# PotDivMUXwithOP_v9.net
KiCad netlist of a schematic drawn in EAGLE
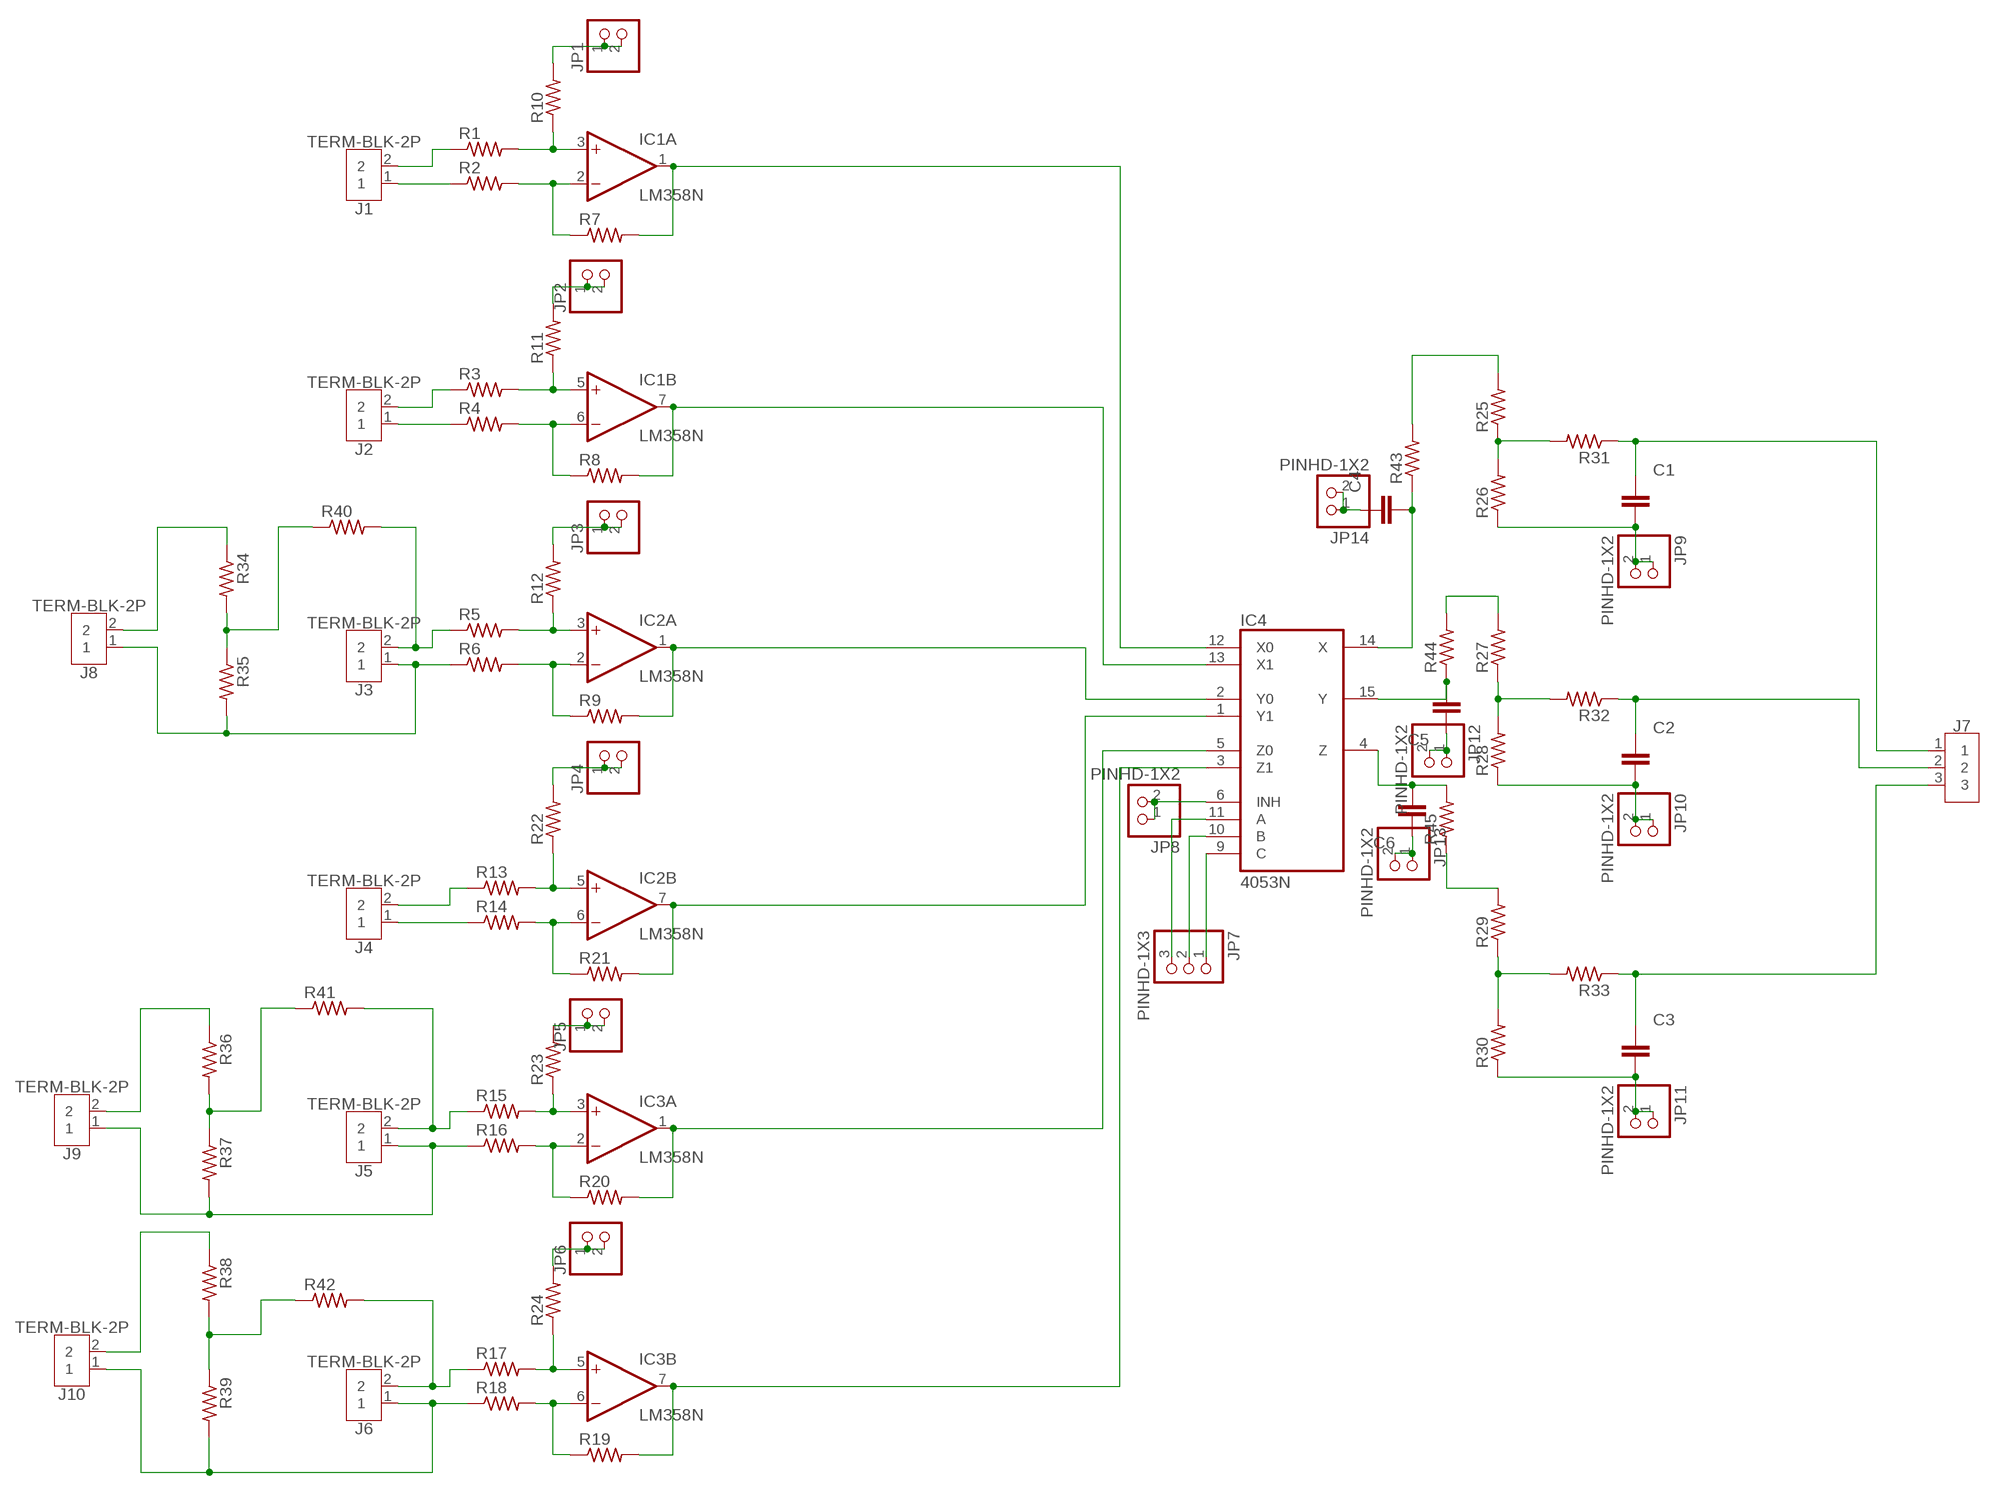
[diagram p0: schematic, sheet 1]

(export (version "E")
  (design (tool "Eeschema 10.0.6"))
  (components
    (comp (ref "C1")
      (value "C_RADIAL-12.5MM-DIA")
      (footprint "eagle-import:CAPRD550W60D1025H1250B")
      (libsource (lib "eagle-import") (part "CRADIAL-12.5MM-DIA_"))
    )
    (comp (ref "C2")
      (value "C_RADIAL-12.5MM-DIA")
      (footprint "eagle-import:CAPRD550W60D1025H1250B")
      (libsource (lib "eagle-import") (part "CRADIAL-12.5MM-DIA_"))
    )
    (comp (ref "C3")
      (value "C_RADIAL-12.5MM-DIA")
      (footprint "eagle-import:CAPRD550W60D1025H1250B")
      (libsource (lib "eagle-import") (part "CRADIAL-12.5MM-DIA_"))
    )
    (comp (ref "C4")
      (value "C_RADIAL-12.5MM-DIA")
      (footprint "eagle-import:CAPRD550W60D1025H1250B")
      (libsource (lib "eagle-import") (part "CRADIAL-12.5MM-DIA_"))
    )
    (comp (ref "C5")
      (value "C_RADIAL-12.5MM-DIA")
      (footprint "eagle-import:CAPRD550W60D1025H1250B")
      (libsource (lib "eagle-import") (part "CRADIAL-12.5MM-DIA_"))
    )
    (comp (ref "C6")
      (value "C_RADIAL-12.5MM-DIA")
      (footprint "eagle-import:CAPRD550W60D1025H1250B")
      (libsource (lib "eagle-import") (part "CRADIAL-12.5MM-DIA_"))
    )
    (comp (ref "IC1")
      (value "LM358N")
      (footprint "eagle-import:DIL08")
      (libsource (lib "eagle-import") (part "LM358N"))
    )
    (comp (ref "IC2")
      (value "LM358N")
      (footprint "eagle-import:DIL08")
      (libsource (lib "eagle-import") (part "LM358N"))
    )
    (comp (ref "IC3")
      (value "LM358N")
      (footprint "eagle-import:DIL08")
      (libsource (lib "eagle-import") (part "LM358N"))
    )
    (comp (ref "IC4")
      (value "4053N")
      (footprint "eagle-import:DIL16")
      (libsource (lib "eagle-import") (part "4053N"))
    )
    (comp (ref "J1")
      (value "TERM-BLK-2P")
      (footprint "eagle-import:TERMBLK_508-2N")
      (fields (field (name "MANUFACTURER") "TE Connectivity AMP Connectors") (field (name "MPN") "282837-2"))
      (libsource (lib "eagle-import") (part "2828XX-2282837-2"))
    )
    (comp (ref "J2")
      (value "TERM-BLK-2P")
      (footprint "eagle-import:TERMBLK_508-2N")
      (fields (field (name "MANUFACTURER") "TE Connectivity AMP Connectors") (field (name "MPN") "282837-2"))
      (libsource (lib "eagle-import") (part "2828XX-2282837-2"))
    )
    (comp (ref "J3")
      (value "TERM-BLK-2P")
      (footprint "eagle-import:TERMBLK_508-2N")
      (fields (field (name "MANUFACTURER") "TE Connectivity AMP Connectors") (field (name "MPN") "282837-2"))
      (libsource (lib "eagle-import") (part "2828XX-2282837-2"))
    )
    (comp (ref "J4")
      (value "TERM-BLK-2P")
      (footprint "eagle-import:TERMBLK_508-2N")
      (fields (field (name "MANUFACTURER") "TE Connectivity AMP Connectors") (field (name "MPN") "282837-2"))
      (libsource (lib "eagle-import") (part "2828XX-2282837-2"))
    )
    (comp (ref "J5")
      (value "TERM-BLK-2P")
      (footprint "eagle-import:TERMBLK_508-2N")
      (fields (field (name "MANUFACTURER") "TE Connectivity AMP Connectors") (field (name "MPN") "282837-2"))
      (libsource (lib "eagle-import") (part "2828XX-2282837-2"))
    )
    (comp (ref "J6")
      (value "TERM-BLK-2P")
      (footprint "eagle-import:TERMBLK_508-2N")
      (fields (field (name "MANUFACTURER") "TE Connectivity AMP Connectors") (field (name "MPN") "282837-2"))
      (libsource (lib "eagle-import") (part "2828XX-2282837-2"))
    )
    (comp (ref "J7")
      (value "TERM-BLK-3P")
      (footprint "eagle-import:TERMBLK_508-3N")
      (fields (field (name "MANUFACTURER") "TE Connectivity") (field (name "MPN") "282837-3"))
      (libsource (lib "eagle-import") (part "2828XX-3282837-3"))
    )
    (comp (ref "J8")
      (value "TERM-BLK-2P")
      (footprint "eagle-import:TERMBLK_508-2N")
      (fields (field (name "MANUFACTURER") "TE Connectivity AMP Connectors") (field (name "MPN") "282837-2"))
      (libsource (lib "eagle-import") (part "2828XX-2282837-2"))
    )
    (comp (ref "J9")
      (value "TERM-BLK-2P")
      (footprint "eagle-import:TERMBLK_508-2N")
      (fields (field (name "MANUFACTURER") "TE Connectivity AMP Connectors") (field (name "MPN") "282837-2"))
      (libsource (lib "eagle-import") (part "2828XX-2282837-2"))
    )
    (comp (ref "J10")
      (value "TERM-BLK-2P")
      (footprint "eagle-import:TERMBLK_508-2N")
      (fields (field (name "MANUFACTURER") "TE Connectivity AMP Connectors") (field (name "MPN") "282837-2"))
      (libsource (lib "eagle-import") (part "2828XX-2282837-2"))
    )
    (comp (ref "JP1")
      (value "PINHD-1X2")
      (footprint "eagle-import:1X02")
      (libsource (lib "eagle-import") (part "pinhead_325_PINHD-1X2"))
    )
    (comp (ref "JP2")
      (value "PINHD-1X2")
      (footprint "eagle-import:1X02")
      (libsource (lib "eagle-import") (part "pinhead_325_PINHD-1X2"))
    )
    (comp (ref "JP3")
      (value "PINHD-1X2")
      (footprint "eagle-import:1X02")
      (libsource (lib "eagle-import") (part "pinhead_325_PINHD-1X2"))
    )
    (comp (ref "JP4")
      (value "PINHD-1X2")
      (footprint "eagle-import:1X02")
      (libsource (lib "eagle-import") (part "pinhead_325_PINHD-1X2"))
    )
    (comp (ref "JP5")
      (value "PINHD-1X2")
      (footprint "eagle-import:1X02")
      (libsource (lib "eagle-import") (part "pinhead_325_PINHD-1X2"))
    )
    (comp (ref "JP6")
      (value "PINHD-1X2")
      (footprint "eagle-import:1X02")
      (libsource (lib "eagle-import") (part "pinhead_325_PINHD-1X2"))
    )
    (comp (ref "JP7")
      (value "PINHD-1X3")
      (footprint "eagle-import:1X03")
      (fields (field (name "MANUFACTURER") "Generic"))
      (libsource (lib "eagle-import") (part "PINHD-1X3"))
    )
    (comp (ref "JP8")
      (value "PINHD-1X2")
      (footprint "eagle-import:1X02")
      (fields (field (name "MANUFACTURER") "Generic"))
      (libsource (lib "eagle-import") (part "PINHD-1X2"))
    )
    (comp (ref "JP9")
      (value "PINHD-1X2")
      (footprint "eagle-import:1X02")
      (fields (field (name "MANUFACTURER") "Generic"))
      (libsource (lib "eagle-import") (part "PINHD-1X2"))
    )
    (comp (ref "JP10")
      (value "PINHD-1X2")
      (footprint "eagle-import:1X02")
      (fields (field (name "MANUFACTURER") "Generic"))
      (libsource (lib "eagle-import") (part "PINHD-1X2"))
    )
    (comp (ref "JP11")
      (value "PINHD-1X2")
      (footprint "eagle-import:1X02")
      (fields (field (name "MANUFACTURER") "Generic"))
      (libsource (lib "eagle-import") (part "PINHD-1X2"))
    )
    (comp (ref "JP12")
      (value "PINHD-1X2")
      (footprint "eagle-import:1X02")
      (fields (field (name "MANUFACTURER") "Generic"))
      (libsource (lib "eagle-import") (part "PINHD-1X2"))
    )
    (comp (ref "JP13")
      (value "PINHD-1X2")
      (footprint "eagle-import:1X02")
      (fields (field (name "MANUFACTURER") "Generic"))
      (libsource (lib "eagle-import") (part "PINHD-1X2"))
    )
    (comp (ref "JP14")
      (value "PINHD-1X2")
      (footprint "eagle-import:1X02")
      (fields (field (name "MANUFACTURER") "Generic"))
      (libsource (lib "eagle-import") (part "PINHD-1X2"))
    )
    (comp (ref "R1")
      (value "R-US_AXIAL-7.2MM-PITCH")
      (footprint "eagle-import:RESAD724W46L381D178B")
      (libsource (lib "eagle-import") (part "R-USAXIAL-7.2MM-PITCH_"))
    )
    (comp (ref "R2")
      (value "R-US_AXIAL-7.2MM-PITCH")
      (footprint "eagle-import:RESAD724W46L381D178B")
      (libsource (lib "eagle-import") (part "R-USAXIAL-7.2MM-PITCH_"))
    )
    (comp (ref "R3")
      (value "R-US_AXIAL-7.2MM-PITCH")
      (footprint "eagle-import:RESAD724W46L381D178B")
      (libsource (lib "eagle-import") (part "R-USAXIAL-7.2MM-PITCH_"))
    )
    (comp (ref "R4")
      (value "R-US_AXIAL-7.2MM-PITCH")
      (footprint "eagle-import:RESAD724W46L381D178B")
      (libsource (lib "eagle-import") (part "R-USAXIAL-7.2MM-PITCH_"))
    )
    (comp (ref "R5")
      (value "R-US_AXIAL-7.2MM-PITCH")
      (footprint "eagle-import:RESAD724W46L381D178B")
      (libsource (lib "eagle-import") (part "R-USAXIAL-7.2MM-PITCH_"))
    )
    (comp (ref "R6")
      (value "R-US_AXIAL-7.2MM-PITCH")
      (footprint "eagle-import:RESAD724W46L381D178B")
      (libsource (lib "eagle-import") (part "R-USAXIAL-7.2MM-PITCH_"))
    )
    (comp (ref "R7")
      (value "R-US_AXIAL-7.2MM-PITCH")
      (footprint "eagle-import:RESAD724W46L381D178B")
      (libsource (lib "eagle-import") (part "R-USAXIAL-7.2MM-PITCH_"))
    )
    (comp (ref "R8")
      (value "R-US_AXIAL-7.2MM-PITCH")
      (footprint "eagle-import:RESAD724W46L381D178B")
      (libsource (lib "eagle-import") (part "R-USAXIAL-7.2MM-PITCH_"))
    )
    (comp (ref "R9")
      (value "R-US_AXIAL-7.2MM-PITCH")
      (footprint "eagle-import:RESAD724W46L381D178B")
      (libsource (lib "eagle-import") (part "R-USAXIAL-7.2MM-PITCH_"))
    )
    (comp (ref "R10")
      (value "R-US_AXIAL-7.2MM-PITCH")
      (footprint "eagle-import:RESAD724W46L381D178B")
      (libsource (lib "eagle-import") (part "R-USAXIAL-7.2MM-PITCH_"))
    )
    (comp (ref "R11")
      (value "R-US_AXIAL-7.2MM-PITCH")
      (footprint "eagle-import:RESAD724W46L381D178B")
      (libsource (lib "eagle-import") (part "R-USAXIAL-7.2MM-PITCH_"))
    )
    (comp (ref "R12")
      (value "R-US_AXIAL-7.2MM-PITCH")
      (footprint "eagle-import:RESAD724W46L381D178B")
      (libsource (lib "eagle-import") (part "R-USAXIAL-7.2MM-PITCH_"))
    )
    (comp (ref "R13")
      (value "R-US_AXIAL-7.2MM-PITCH")
      (footprint "eagle-import:RESAD724W46L381D178B")
      (libsource (lib "eagle-import") (part "R-USAXIAL-7.2MM-PITCH_"))
    )
    (comp (ref "R14")
      (value "R-US_AXIAL-7.2MM-PITCH")
      (footprint "eagle-import:RESAD724W46L381D178B")
      (libsource (lib "eagle-import") (part "R-USAXIAL-7.2MM-PITCH_"))
    )
    (comp (ref "R15")
      (value "R-US_AXIAL-7.2MM-PITCH")
      (footprint "eagle-import:RESAD724W46L381D178B")
      (libsource (lib "eagle-import") (part "R-USAXIAL-7.2MM-PITCH_"))
    )
    (comp (ref "R16")
      (value "R-US_AXIAL-7.2MM-PITCH")
      (footprint "eagle-import:RESAD724W46L381D178B")
      (libsource (lib "eagle-import") (part "R-USAXIAL-7.2MM-PITCH_"))
    )
    (comp (ref "R17")
      (value "R-US_AXIAL-7.2MM-PITCH")
      (footprint "eagle-import:RESAD724W46L381D178B")
      (libsource (lib "eagle-import") (part "R-USAXIAL-7.2MM-PITCH_"))
    )
    (comp (ref "R18")
      (value "R-US_AXIAL-7.2MM-PITCH")
      (footprint "eagle-import:RESAD724W46L381D178B")
      (libsource (lib "eagle-import") (part "R-USAXIAL-7.2MM-PITCH_"))
    )
    (comp (ref "R19")
      (value "R-US_AXIAL-7.2MM-PITCH")
      (footprint "eagle-import:RESAD724W46L381D178B")
      (libsource (lib "eagle-import") (part "R-USAXIAL-7.2MM-PITCH_"))
    )
    (comp (ref "R20")
      (value "R-US_AXIAL-7.2MM-PITCH")
      (footprint "eagle-import:RESAD724W46L381D178B")
      (libsource (lib "eagle-import") (part "R-USAXIAL-7.2MM-PITCH_"))
    )
    (comp (ref "R21")
      (value "R-US_AXIAL-7.2MM-PITCH")
      (footprint "eagle-import:RESAD724W46L381D178B")
      (libsource (lib "eagle-import") (part "R-USAXIAL-7.2MM-PITCH_"))
    )
    (comp (ref "R22")
      (value "R-US_AXIAL-7.2MM-PITCH")
      (footprint "eagle-import:RESAD724W46L381D178B")
      (libsource (lib "eagle-import") (part "R-USAXIAL-7.2MM-PITCH_"))
    )
    (comp (ref "R23")
      (value "R-US_AXIAL-7.2MM-PITCH")
      (footprint "eagle-import:RESAD724W46L381D178B")
      (libsource (lib "eagle-import") (part "R-USAXIAL-7.2MM-PITCH_"))
    )
    (comp (ref "R24")
      (value "R-US_AXIAL-7.2MM-PITCH")
      (footprint "eagle-import:RESAD724W46L381D178B")
      (libsource (lib "eagle-import") (part "R-USAXIAL-7.2MM-PITCH_"))
    )
    (comp (ref "R25")
      (value "R-US_AXIAL-7.2MM-PITCH")
      (footprint "eagle-import:RESAD724W46L381D178B")
      (libsource (lib "eagle-import") (part "R-USAXIAL-7.2MM-PITCH_"))
    )
    (comp (ref "R26")
      (value "R-US_AXIAL-7.2MM-PITCH")
      (footprint "eagle-import:RESAD724W46L381D178B")
      (libsource (lib "eagle-import") (part "R-USAXIAL-7.2MM-PITCH_"))
    )
    (comp (ref "R27")
      (value "R-US_AXIAL-7.2MM-PITCH")
      (footprint "eagle-import:RESAD724W46L381D178B")
      (libsource (lib "eagle-import") (part "R-USAXIAL-7.2MM-PITCH_"))
    )
    (comp (ref "R28")
      (value "R-US_AXIAL-7.2MM-PITCH")
      (footprint "eagle-import:RESAD724W46L381D178B")
      (libsource (lib "eagle-import") (part "R-USAXIAL-7.2MM-PITCH_"))
    )
    (comp (ref "R29")
      (value "R-US_AXIAL-7.2MM-PITCH")
      (footprint "eagle-import:RESAD724W46L381D178B")
      (libsource (lib "eagle-import") (part "R-USAXIAL-7.2MM-PITCH_"))
    )
    (comp (ref "R30")
      (value "R-US_AXIAL-7.2MM-PITCH")
      (footprint "eagle-import:RESAD724W46L381D178B")
      (libsource (lib "eagle-import") (part "R-USAXIAL-7.2MM-PITCH_"))
    )
    (comp (ref "R31")
      (value "R-US_AXIAL-7.2MM-PITCH")
      (footprint "eagle-import:RESAD724W46L381D178B")
      (libsource (lib "eagle-import") (part "R-USAXIAL-7.2MM-PITCH_"))
    )
    (comp (ref "R32")
      (value "R-US_AXIAL-7.2MM-PITCH")
      (footprint "eagle-import:RESAD724W46L381D178B")
      (libsource (lib "eagle-import") (part "R-USAXIAL-7.2MM-PITCH_"))
    )
    (comp (ref "R33")
      (value "R-US_AXIAL-7.2MM-PITCH")
      (footprint "eagle-import:RESAD724W46L381D178B")
      (libsource (lib "eagle-import") (part "R-USAXIAL-7.2MM-PITCH_"))
    )
    (comp (ref "R34")
      (value "R-US_AXIAL-7.2MM-PITCH")
      (footprint "eagle-import:RESAD724W46L381D178B")
      (libsource (lib "eagle-import") (part "R-USAXIAL-7.2MM-PITCH_"))
    )
    (comp (ref "R35")
      (value "R-US_AXIAL-7.2MM-PITCH")
      (footprint "eagle-import:RESAD724W46L381D178B")
      (libsource (lib "eagle-import") (part "R-USAXIAL-7.2MM-PITCH_"))
    )
    (comp (ref "R36")
      (value "R-US_AXIAL-7.2MM-PITCH")
      (footprint "eagle-import:RESAD724W46L381D178B")
      (libsource (lib "eagle-import") (part "R-USAXIAL-7.2MM-PITCH_"))
    )
    (comp (ref "R37")
      (value "R-US_AXIAL-7.2MM-PITCH")
      (footprint "eagle-import:RESAD724W46L381D178B")
      (libsource (lib "eagle-import") (part "R-USAXIAL-7.2MM-PITCH_"))
    )
    (comp (ref "R38")
      (value "R-US_AXIAL-7.2MM-PITCH")
      (footprint "eagle-import:RESAD724W46L381D178B")
      (libsource (lib "eagle-import") (part "R-USAXIAL-7.2MM-PITCH_"))
    )
    (comp (ref "R39")
      (value "R-US_AXIAL-7.2MM-PITCH")
      (footprint "eagle-import:RESAD724W46L381D178B")
      (libsource (lib "eagle-import") (part "R-USAXIAL-7.2MM-PITCH_"))
    )
    (comp (ref "R40")
      (value "R-US_AXIAL-7.2MM-PITCH")
      (footprint "eagle-import:RESAD724W46L381D178B")
      (libsource (lib "eagle-import") (part "R-USAXIAL-7.2MM-PITCH_"))
    )
    (comp (ref "R41")
      (value "R-US_AXIAL-7.2MM-PITCH")
      (footprint "eagle-import:RESAD724W46L381D178B")
      (libsource (lib "eagle-import") (part "R-USAXIAL-7.2MM-PITCH_"))
    )
    (comp (ref "R42")
      (value "R-US_AXIAL-7.2MM-PITCH")
      (footprint "eagle-import:RESAD724W46L381D178B")
      (libsource (lib "eagle-import") (part "R-USAXIAL-7.2MM-PITCH_"))
    )
    (comp (ref "R43")
      (value "R-US_AXIAL-7.2MM-PITCH")
      (footprint "eagle-import:RESAD724W46L381D178B")
      (libsource (lib "eagle-import") (part "R-USAXIAL-7.2MM-PITCH_"))
    )
    (comp (ref "R44")
      (value "R-US_AXIAL-7.2MM-PITCH")
      (footprint "eagle-import:RESAD724W46L381D178B")
      (libsource (lib "eagle-import") (part "R-USAXIAL-7.2MM-PITCH_"))
    )
    (comp (ref "R45")
      (value "R-US_AXIAL-7.2MM-PITCH")
      (footprint "eagle-import:RESAD724W46L381D178B")
      (libsource (lib "eagle-import") (part "R-USAXIAL-7.2MM-PITCH_"))
    )
  )
  (nets
    (net (code "1") (name "Net-(C1-Pad1)") (class "Default")
      (node (ref "C1") (pin "1") (pinfunction "1_1") (pintype "passive"))
      (node (ref "J7") (pin "1") (pinfunction "1_1") (pintype "bidirectional"))
      (node (ref "R31") (pin "1") (pinfunction "1_1") (pintype "passive"))
    )
    (net (code "2") (name "Net-(C1-Pad2)") (class "Default")
      (node (ref "C1") (pin "2") (pinfunction "2_2") (pintype "passive"))
      (node (ref "JP9") (pin "1") (pinfunction "1_1") (pintype "passive"))
      (node (ref "JP9") (pin "2") (pinfunction "2_2") (pintype "passive"))
      (node (ref "R26") (pin "1") (pinfunction "1_1") (pintype "passive"))
    )
    (net (code "3") (name "Net-(C2-Pad1)") (class "Default")
      (node (ref "C2") (pin "1") (pinfunction "1_1") (pintype "passive"))
      (node (ref "J7") (pin "2") (pinfunction "2_2") (pintype "bidirectional"))
      (node (ref "R32") (pin "1") (pinfunction "1_1") (pintype "passive"))
    )
    (net (code "4") (name "Net-(C2-Pad2)") (class "Default")
      (node (ref "C2") (pin "2") (pinfunction "2_2") (pintype "passive"))
      (node (ref "JP10") (pin "1") (pinfunction "1_1") (pintype "passive"))
      (node (ref "JP10") (pin "2") (pinfunction "2_2") (pintype "passive"))
      (node (ref "R28") (pin "1") (pinfunction "1_1") (pintype "passive"))
    )
    (net (code "5") (name "Net-(C3-Pad1)") (class "Default")
      (node (ref "C3") (pin "1") (pinfunction "1_1") (pintype "passive"))
      (node (ref "J7") (pin "3") (pinfunction "3_3") (pintype "bidirectional"))
      (node (ref "R33") (pin "1") (pinfunction "1_1") (pintype "passive"))
    )
    (net (code "6") (name "Net-(C3-Pad2)") (class "Default")
      (node (ref "C3") (pin "2") (pinfunction "2_2") (pintype "passive"))
      (node (ref "JP11") (pin "1") (pinfunction "1_1") (pintype "passive"))
      (node (ref "JP11") (pin "2") (pinfunction "2_2") (pintype "passive"))
      (node (ref "R30") (pin "1") (pinfunction "1_1") (pintype "passive"))
    )
    (net (code "7") (name "Net-(C4-Pad1)") (class "Default")
      (node (ref "C4") (pin "1") (pinfunction "1_1") (pintype "passive"))
      (node (ref "JP14") (pin "1") (pinfunction "1_1") (pintype "passive"))
      (node (ref "JP14") (pin "2") (pinfunction "2_2") (pintype "passive"))
    )
    (net (code "8") (name "Net-(C5-Pad1)") (class "Default")
      (node (ref "C5") (pin "1") (pinfunction "1_1") (pintype "passive"))
      (node (ref "JP12") (pin "1") (pinfunction "1_1") (pintype "passive"))
      (node (ref "JP12") (pin "2") (pinfunction "2_2") (pintype "passive"))
    )
    (net (code "9") (name "Net-(C6-Pad1)") (class "Default")
      (node (ref "C6") (pin "1") (pinfunction "1_1") (pintype "passive"))
      (node (ref "JP13") (pin "1") (pinfunction "1_1") (pintype "passive"))
      (node (ref "JP13") (pin "2") (pinfunction "2_2") (pintype "passive"))
    )
    (net (code "10") (name "Net-(IC1A-+IN)") (class "Default")
      (node (ref "IC1") (pin "3") (pinfunction "+IN_3") (pintype "input"))
      (node (ref "R1") (pin "2") (pinfunction "2_2") (pintype "passive"))
      (node (ref "R10") (pin "1") (pinfunction "1_1") (pintype "passive"))
    )
    (net (code "11") (name "Net-(IC1A--IN)") (class "Default")
      (node (ref "IC1") (pin "2") (pinfunction "-IN_2") (pintype "input"))
      (node (ref "R2") (pin "2") (pinfunction "2_2") (pintype "passive"))
      (node (ref "R7") (pin "1") (pinfunction "1_1") (pintype "passive"))
    )
    (net (code "12") (name "Net-(IC1A-OUT)") (class "Default")
      (node (ref "IC1") (pin "1") (pinfunction "OUT_1") (pintype "output"))
      (node (ref "IC4") (pin "12") (pinfunction "X0_12") (pintype "bidirectional"))
      (node (ref "R7") (pin "2") (pinfunction "2_2") (pintype "passive"))
    )
    (net (code "13") (name "Net-(IC1B-+IN)") (class "Default")
      (node (ref "IC1") (pin "5") (pinfunction "+IN_5") (pintype "input"))
      (node (ref "R11") (pin "1") (pinfunction "1_1") (pintype "passive"))
      (node (ref "R3") (pin "2") (pinfunction "2_2") (pintype "passive"))
    )
    (net (code "14") (name "Net-(IC1B--IN)") (class "Default")
      (node (ref "IC1") (pin "6") (pinfunction "-IN_6") (pintype "input"))
      (node (ref "R4") (pin "2") (pinfunction "2_2") (pintype "passive"))
      (node (ref "R8") (pin "1") (pinfunction "1_1") (pintype "passive"))
    )
    (net (code "15") (name "Net-(IC1B-OUT)") (class "Default")
      (node (ref "IC1") (pin "7") (pinfunction "OUT_7") (pintype "output"))
      (node (ref "IC4") (pin "13") (pinfunction "X1_13") (pintype "bidirectional"))
      (node (ref "R8") (pin "2") (pinfunction "2_2") (pintype "passive"))
    )
    (net (code "16") (name "Net-(IC2A-+IN)") (class "Default")
      (node (ref "IC2") (pin "3") (pinfunction "+IN_3") (pintype "input"))
      (node (ref "R12") (pin "1") (pinfunction "1_1") (pintype "passive"))
      (node (ref "R5") (pin "2") (pinfunction "2_2") (pintype "passive"))
    )
    (net (code "17") (name "Net-(IC2A--IN)") (class "Default")
      (node (ref "IC2") (pin "2") (pinfunction "-IN_2") (pintype "input"))
      (node (ref "R6") (pin "2") (pinfunction "2_2") (pintype "passive"))
      (node (ref "R9") (pin "1") (pinfunction "1_1") (pintype "passive"))
    )
    (net (code "18") (name "Net-(IC2A-OUT)") (class "Default")
      (node (ref "IC2") (pin "1") (pinfunction "OUT_1") (pintype "output"))
      (node (ref "IC4") (pin "2") (pinfunction "Y0_2") (pintype "bidirectional"))
      (node (ref "R9") (pin "2") (pinfunction "2_2") (pintype "passive"))
    )
    (net (code "19") (name "Net-(IC2B-+IN)") (class "Default")
      (node (ref "IC2") (pin "5") (pinfunction "+IN_5") (pintype "input"))
      (node (ref "R13") (pin "2") (pinfunction "2_2") (pintype "passive"))
      (node (ref "R22") (pin "1") (pinfunction "1_1") (pintype "passive"))
    )
    (net (code "20") (name "Net-(IC2B--IN)") (class "Default")
      (node (ref "IC2") (pin "6") (pinfunction "-IN_6") (pintype "input"))
      (node (ref "R14") (pin "2") (pinfunction "2_2") (pintype "passive"))
      (node (ref "R21") (pin "1") (pinfunction "1_1") (pintype "passive"))
    )
    (net (code "21") (name "Net-(IC2B-OUT)") (class "Default")
      (node (ref "IC2") (pin "7") (pinfunction "OUT_7") (pintype "output"))
      (node (ref "IC4") (pin "1") (pinfunction "Y1_1") (pintype "bidirectional"))
      (node (ref "R21") (pin "2") (pinfunction "2_2") (pintype "passive"))
    )
    (net (code "22") (name "Net-(IC3A-+IN)") (class "Default")
      (node (ref "IC3") (pin "3") (pinfunction "+IN_3") (pintype "input"))
      (node (ref "R15") (pin "2") (pinfunction "2_2") (pintype "passive"))
      (node (ref "R23") (pin "1") (pinfunction "1_1") (pintype "passive"))
    )
    (net (code "23") (name "Net-(IC3A--IN)") (class "Default")
      (node (ref "IC3") (pin "2") (pinfunction "-IN_2") (pintype "input"))
      (node (ref "R16") (pin "2") (pinfunction "2_2") (pintype "passive"))
      (node (ref "R20") (pin "1") (pinfunction "1_1") (pintype "passive"))
    )
    (net (code "24") (name "Net-(IC3A-OUT)") (class "Default")
      (node (ref "IC3") (pin "1") (pinfunction "OUT_1") (pintype "output"))
      (node (ref "IC4") (pin "5") (pinfunction "Z0_5") (pintype "bidirectional"))
      (node (ref "R20") (pin "2") (pinfunction "2_2") (pintype "passive"))
    )
    (net (code "25") (name "Net-(IC3B-+IN)") (class "Default")
      (node (ref "IC3") (pin "5") (pinfunction "+IN_5") (pintype "input"))
      (node (ref "R17") (pin "2") (pinfunction "2_2") (pintype "passive"))
      (node (ref "R24") (pin "1") (pinfunction "1_1") (pintype "passive"))
    )
    (net (code "26") (name "Net-(IC3B--IN)") (class "Default")
      (node (ref "IC3") (pin "6") (pinfunction "-IN_6") (pintype "input"))
      (node (ref "R18") (pin "2") (pinfunction "2_2") (pintype "passive"))
      (node (ref "R19") (pin "1") (pinfunction "1_1") (pintype "passive"))
    )
    (net (code "27") (name "Net-(IC3B-OUT)") (class "Default")
      (node (ref "IC3") (pin "7") (pinfunction "OUT_7") (pintype "output"))
      (node (ref "IC4") (pin "3") (pinfunction "Z1_3") (pintype "bidirectional"))
      (node (ref "R19") (pin "2") (pinfunction "2_2") (pintype "passive"))
    )
    (net (code "28") (name "Net-(IC4A-A)") (class "Default")
      (node (ref "IC4") (pin "11") (pinfunction "A_11") (pintype "input"))
      (node (ref "JP7") (pin "3") (pinfunction "3_3") (pintype "passive"))
    )
    (net (code "29") (name "Net-(IC4A-B)") (class "Default")
      (node (ref "IC4") (pin "10") (pinfunction "B_10") (pintype "input"))
      (node (ref "JP7") (pin "2") (pinfunction "2_2") (pintype "passive"))
    )
    (net (code "30") (name "Net-(IC4A-C)") (class "Default")
      (node (ref "IC4") (pin "9") (pinfunction "C_9") (pintype "input"))
      (node (ref "JP7") (pin "1") (pinfunction "1_1") (pintype "passive"))
    )
    (net (code "31") (name "Net-(IC4A-INH)") (class "Default")
      (node (ref "IC4") (pin "6") (pinfunction "INH_6") (pintype "input"))
      (node (ref "JP8") (pin "1") (pinfunction "1_1") (pintype "passive"))
      (node (ref "JP8") (pin "2") (pinfunction "2_2") (pintype "passive"))
    )
    (net (code "32") (name "Net-(IC4A-X)") (class "Default")
      (node (ref "C4") (pin "2") (pinfunction "2_2") (pintype "passive"))
      (node (ref "IC4") (pin "14") (pinfunction "X_14") (pintype "bidirectional"))
      (node (ref "R43") (pin "1") (pinfunction "1_1") (pintype "passive"))
    )
    (net (code "33") (name "Net-(IC4A-Y)") (class "Default")
      (node (ref "C5") (pin "2") (pinfunction "2_2") (pintype "passive"))
      (node (ref "IC4") (pin "15") (pinfunction "Y_15") (pintype "bidirectional"))
      (node (ref "R44") (pin "1") (pinfunction "1_1") (pintype "passive"))
    )
    (net (code "34") (name "Net-(IC4A-Z)") (class "Default")
      (node (ref "C6") (pin "2") (pinfunction "2_2") (pintype "passive"))
      (node (ref "IC4") (pin "4") (pinfunction "Z_4") (pintype "bidirectional"))
      (node (ref "R45") (pin "2") (pinfunction "2_2") (pintype "passive"))
    )
    (net (code "35") (name "Net-(J1-Pad1)") (class "Default")
      (node (ref "J1") (pin "1") (pinfunction "1_1") (pintype "bidirectional"))
      (node (ref "R2") (pin "1") (pinfunction "1_1") (pintype "passive"))
    )
    (net (code "36") (name "Net-(J1-Pad2)") (class "Default")
      (node (ref "J1") (pin "2") (pinfunction "2_2") (pintype "bidirectional"))
      (node (ref "R1") (pin "1") (pinfunction "1_1") (pintype "passive"))
    )
    (net (code "37") (name "Net-(J2-Pad1)") (class "Default")
      (node (ref "J2") (pin "1") (pinfunction "1_1") (pintype "bidirectional"))
      (node (ref "R4") (pin "1") (pinfunction "1_1") (pintype "passive"))
    )
    (net (code "38") (name "Net-(J2-Pad2)") (class "Default")
      (node (ref "J2") (pin "2") (pinfunction "2_2") (pintype "bidirectional"))
      (node (ref "R3") (pin "1") (pinfunction "1_1") (pintype "passive"))
    )
    (net (code "39") (name "Net-(J3-Pad1)") (class "Default")
      (node (ref "J3") (pin "1") (pinfunction "1_1") (pintype "bidirectional"))
      (node (ref "J8") (pin "1") (pinfunction "1_1") (pintype "bidirectional"))
      (node (ref "R35") (pin "2") (pinfunction "2_2") (pintype "passive"))
      (node (ref "R6") (pin "1") (pinfunction "1_1") (pintype "passive"))
    )
    (net (code "40") (name "Net-(J3-Pad2)") (class "Default")
      (node (ref "J3") (pin "2") (pinfunction "2_2") (pintype "bidirectional"))
      (node (ref "R40") (pin "2") (pinfunction "2_2") (pintype "passive"))
      (node (ref "R5") (pin "1") (pinfunction "1_1") (pintype "passive"))
    )
    (net (code "41") (name "Net-(J4-Pad1)") (class "Default")
      (node (ref "J4") (pin "1") (pinfunction "1_1") (pintype "bidirectional"))
      (node (ref "R14") (pin "1") (pinfunction "1_1") (pintype "passive"))
    )
    (net (code "42") (name "Net-(J4-Pad2)") (class "Default")
      (node (ref "J4") (pin "2") (pinfunction "2_2") (pintype "bidirectional"))
      (node (ref "R13") (pin "1") (pinfunction "1_1") (pintype "passive"))
    )
    (net (code "43") (name "Net-(J5-Pad1)") (class "Default")
      (node (ref "J5") (pin "1") (pinfunction "1_1") (pintype "bidirectional"))
      (node (ref "J9") (pin "1") (pinfunction "1_1") (pintype "bidirectional"))
      (node (ref "R16") (pin "1") (pinfunction "1_1") (pintype "passive"))
      (node (ref "R37") (pin "2") (pinfunction "2_2") (pintype "passive"))
    )
    (net (code "44") (name "Net-(J5-Pad2)") (class "Default")
      (node (ref "J5") (pin "2") (pinfunction "2_2") (pintype "bidirectional"))
      (node (ref "R15") (pin "1") (pinfunction "1_1") (pintype "passive"))
      (node (ref "R41") (pin "2") (pinfunction "2_2") (pintype "passive"))
    )
    (net (code "45") (name "Net-(J6-Pad2)") (class "Default")
      (node (ref "J6") (pin "2") (pinfunction "2_2") (pintype "bidirectional"))
      (node (ref "R17") (pin "1") (pinfunction "1_1") (pintype "passive"))
      (node (ref "R42") (pin "2") (pinfunction "2_2") (pintype "passive"))
    )
    (net (code "46") (name "Net-(J8-Pad2)") (class "Default")
      (node (ref "J8") (pin "2") (pinfunction "2_2") (pintype "bidirectional"))
      (node (ref "R34") (pin "1") (pinfunction "1_1") (pintype "passive"))
    )
    (net (code "47") (name "Net-(J9-Pad2)") (class "Default")
      (node (ref "J9") (pin "2") (pinfunction "2_2") (pintype "bidirectional"))
      (node (ref "R36") (pin "1") (pinfunction "1_1") (pintype "passive"))
    )
    (net (code "48") (name "Net-(J10-Pad1)") (class "Default")
      (node (ref "J10") (pin "1") (pinfunction "1_1") (pintype "bidirectional"))
      (node (ref "J6") (pin "1") (pinfunction "1_1") (pintype "bidirectional"))
      (node (ref "R18") (pin "1") (pinfunction "1_1") (pintype "passive"))
      (node (ref "R39") (pin "2") (pinfunction "2_2") (pintype "passive"))
    )
    (net (code "49") (name "Net-(J10-Pad2)") (class "Default")
      (node (ref "J10") (pin "2") (pinfunction "2_2") (pintype "bidirectional"))
      (node (ref "R38") (pin "1") (pinfunction "1_1") (pintype "passive"))
    )
    (net (code "50") (name "Net-(JP1-Pad1)") (class "Default")
      (node (ref "JP1") (pin "1") (pinfunction "1_1") (pintype "passive"))
      (node (ref "JP1") (pin "2") (pinfunction "2_2") (pintype "passive"))
      (node (ref "R10") (pin "2") (pinfunction "2_2") (pintype "passive"))
    )
    (net (code "51") (name "Net-(JP2-Pad1)") (class "Default")
      (node (ref "JP2") (pin "1") (pinfunction "1_1") (pintype "passive"))
      (node (ref "JP2") (pin "2") (pinfunction "2_2") (pintype "passive"))
      (node (ref "R11") (pin "2") (pinfunction "2_2") (pintype "passive"))
    )
    (net (code "52") (name "Net-(JP3-Pad1)") (class "Default")
      (node (ref "JP3") (pin "1") (pinfunction "1_1") (pintype "passive"))
      (node (ref "JP3") (pin "2") (pinfunction "2_2") (pintype "passive"))
      (node (ref "R12") (pin "2") (pinfunction "2_2") (pintype "passive"))
    )
    (net (code "53") (name "Net-(JP4-Pad1)") (class "Default")
      (node (ref "JP4") (pin "1") (pinfunction "1_1") (pintype "passive"))
      (node (ref "JP4") (pin "2") (pinfunction "2_2") (pintype "passive"))
      (node (ref "R22") (pin "2") (pinfunction "2_2") (pintype "passive"))
    )
    (net (code "54") (name "Net-(JP5-Pad1)") (class "Default")
      (node (ref "JP5") (pin "1") (pinfunction "1_1") (pintype "passive"))
      (node (ref "JP5") (pin "2") (pinfunction "2_2") (pintype "passive"))
      (node (ref "R23") (pin "2") (pinfunction "2_2") (pintype "passive"))
    )
    (net (code "55") (name "Net-(JP6-Pad1)") (class "Default")
      (node (ref "JP6") (pin "1") (pinfunction "1_1") (pintype "passive"))
      (node (ref "JP6") (pin "2") (pinfunction "2_2") (pintype "passive"))
      (node (ref "R24") (pin "2") (pinfunction "2_2") (pintype "passive"))
    )
    (net (code "56") (name "Net-(R25-Pad1)") (class "Default")
      (node (ref "R25") (pin "1") (pinfunction "1_1") (pintype "passive"))
      (node (ref "R26") (pin "2") (pinfunction "2_2") (pintype "passive"))
      (node (ref "R31") (pin "2") (pinfunction "2_2") (pintype "passive"))
    )
    (net (code "57") (name "Net-(R25-Pad2)") (class "Default")
      (node (ref "R25") (pin "2") (pinfunction "2_2") (pintype "passive"))
      (node (ref "R43") (pin "2") (pinfunction "2_2") (pintype "passive"))
    )
    (net (code "58") (name "Net-(R27-Pad1)") (class "Default")
      (node (ref "R27") (pin "1") (pinfunction "1_1") (pintype "passive"))
      (node (ref "R28") (pin "2") (pinfunction "2_2") (pintype "passive"))
      (node (ref "R32") (pin "2") (pinfunction "2_2") (pintype "passive"))
    )
    (net (code "59") (name "Net-(R27-Pad2)") (class "Default")
      (node (ref "R27") (pin "2") (pinfunction "2_2") (pintype "passive"))
      (node (ref "R44") (pin "2") (pinfunction "2_2") (pintype "passive"))
    )
    (net (code "60") (name "Net-(R29-Pad1)") (class "Default")
      (node (ref "R29") (pin "1") (pinfunction "1_1") (pintype "passive"))
      (node (ref "R30") (pin "2") (pinfunction "2_2") (pintype "passive"))
      (node (ref "R33") (pin "2") (pinfunction "2_2") (pintype "passive"))
    )
    (net (code "61") (name "Net-(R29-Pad2)") (class "Default")
      (node (ref "R29") (pin "2") (pinfunction "2_2") (pintype "passive"))
      (node (ref "R45") (pin "1") (pinfunction "1_1") (pintype "passive"))
    )
    (net (code "62") (name "Net-(R34-Pad2)") (class "Default")
      (node (ref "R34") (pin "2") (pinfunction "2_2") (pintype "passive"))
      (node (ref "R35") (pin "1") (pinfunction "1_1") (pintype "passive"))
      (node (ref "R40") (pin "1") (pinfunction "1_1") (pintype "passive"))
    )
    (net (code "63") (name "Net-(R36-Pad2)") (class "Default")
      (node (ref "R36") (pin "2") (pinfunction "2_2") (pintype "passive"))
      (node (ref "R37") (pin "1") (pinfunction "1_1") (pintype "passive"))
      (node (ref "R41") (pin "1") (pinfunction "1_1") (pintype "passive"))
    )
    (net (code "64") (name "Net-(R38-Pad2)") (class "Default")
      (node (ref "R38") (pin "2") (pinfunction "2_2") (pintype "passive"))
      (node (ref "R39") (pin "1") (pinfunction "1_1") (pintype "passive"))
      (node (ref "R42") (pin "1") (pinfunction "1_1") (pintype "passive"))
    )
  )
)
